# Sheet1.net
KiCad netlist of a schematic drawn in Altium Designer
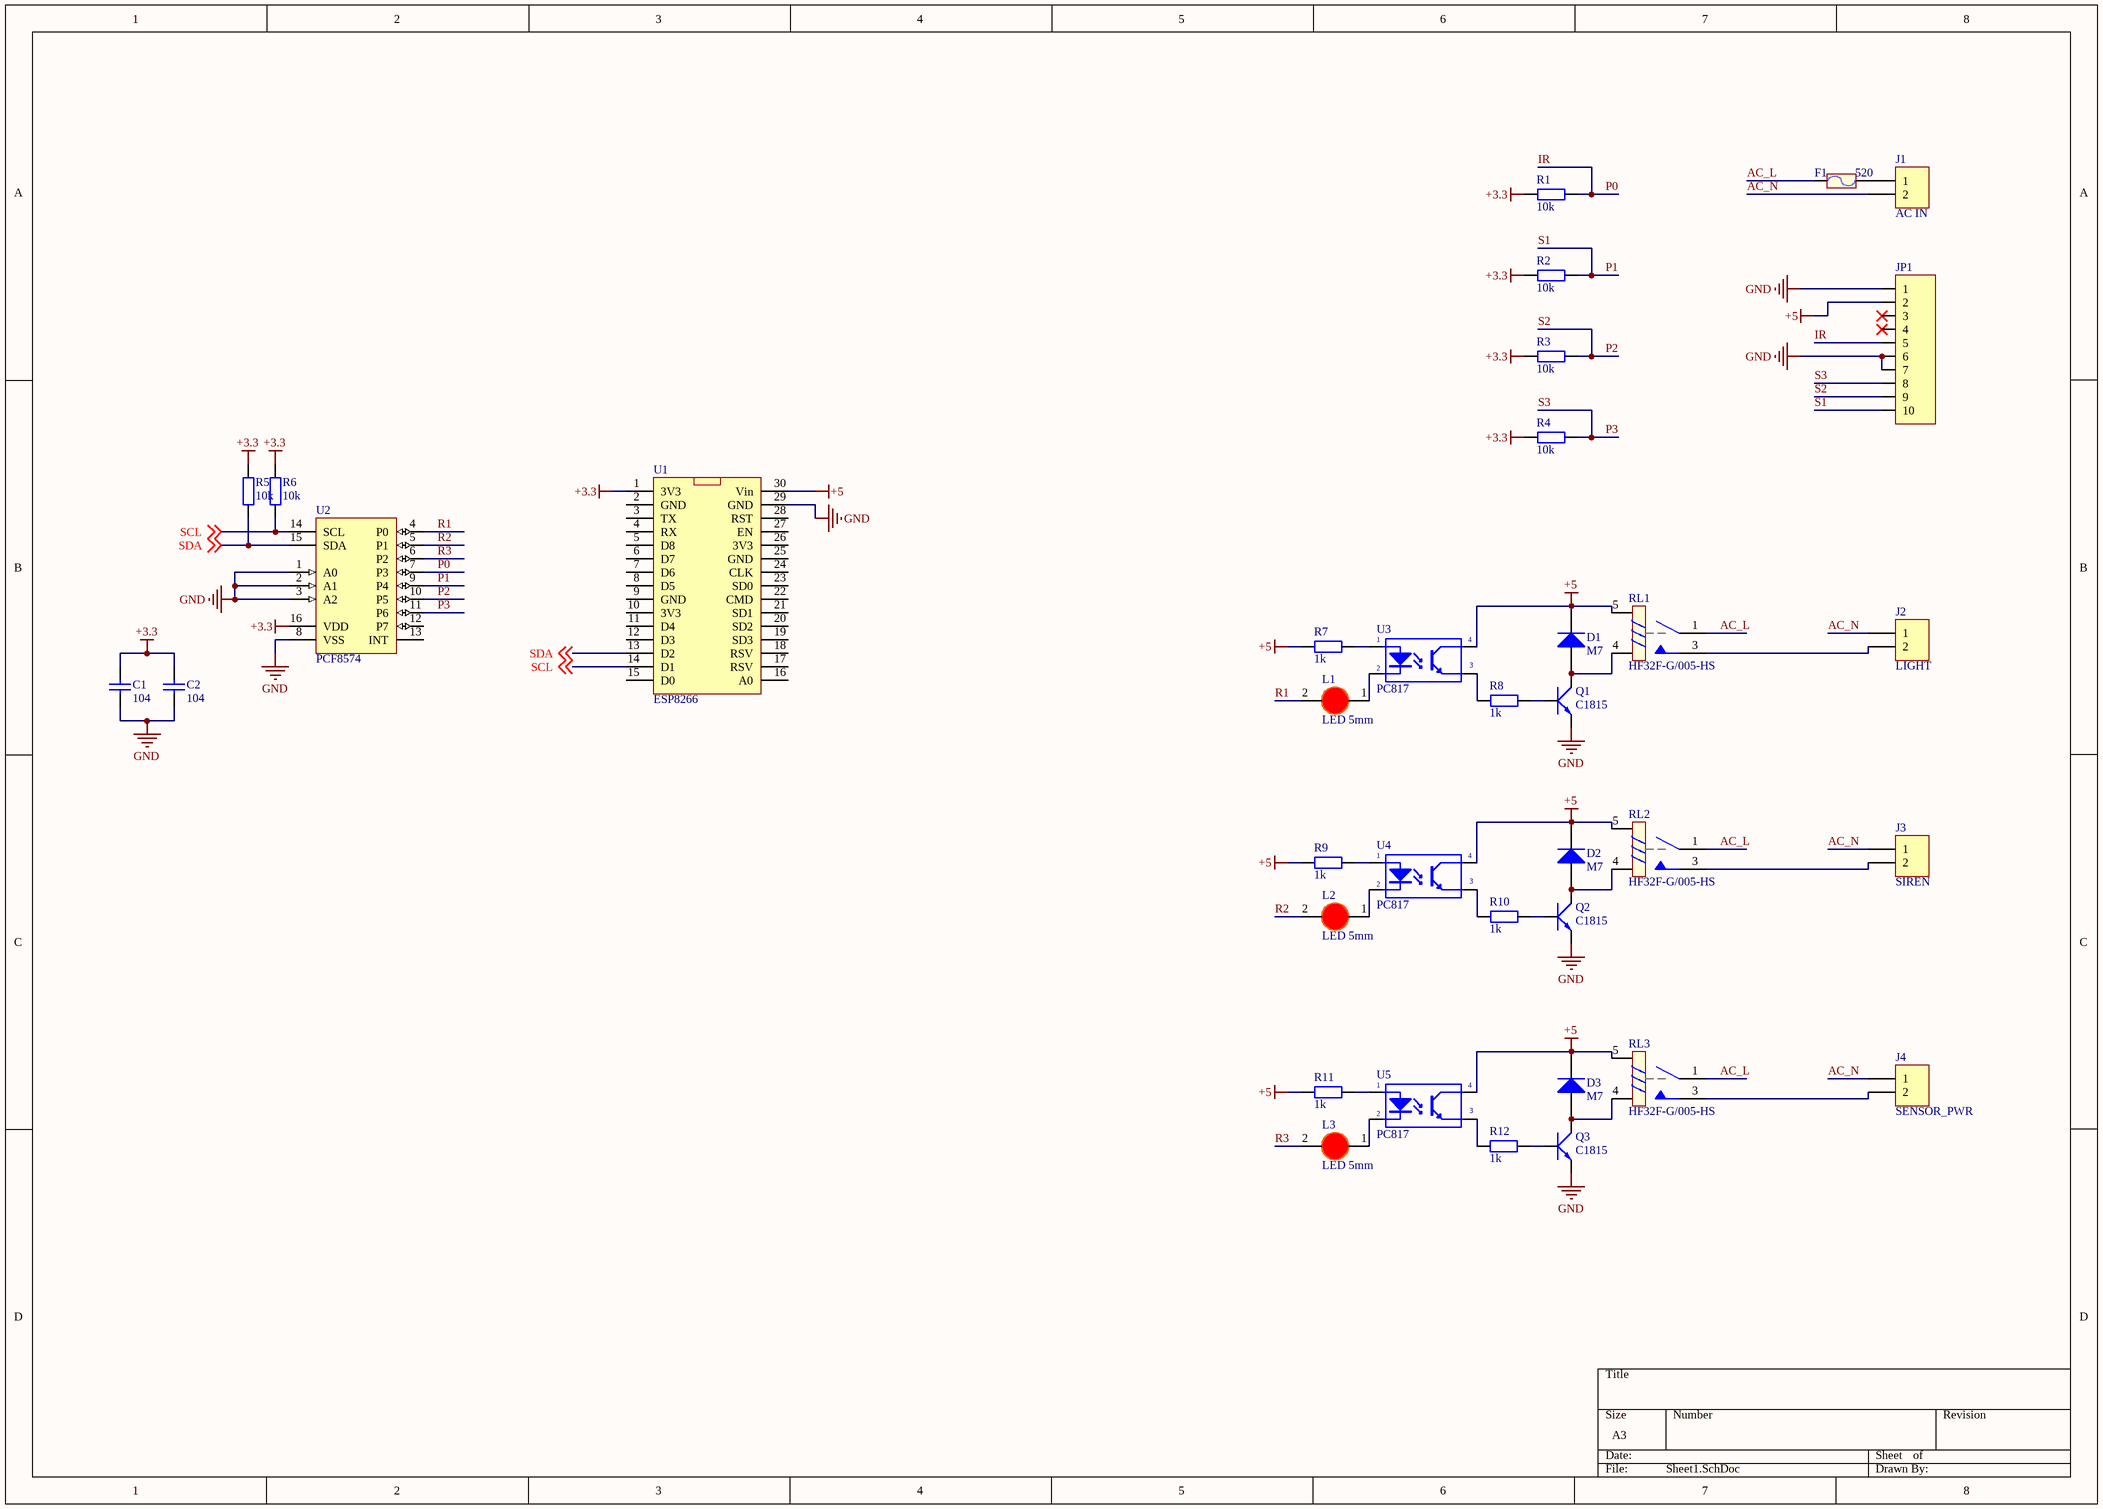
[diagram p0: Sheet1.SchDoc]

(export (version "E")
  (design (tool "Eeschema 10.0.6"))
  (components
    (comp (ref "C1")
      (value "104")
      (footprint "tu 0805")
      (description "Dán")
      (libsource (lib "Altium_Lib_by_KhueNguyenCreator") (part "Tu 0805 104 50V 10%"))
    )
    (comp (ref "C2")
      (value "104")
      (footprint "tu 0805")
      (description "Dán")
      (libsource (lib "Altium_Lib_by_KhueNguyenCreator") (part "Tu 0805 104 50V 10%"))
    )
    (comp (ref "D1")
      (value "M7")
      (footprint "DIODE SMA")
      (description "Dán")
      (libsource (lib "Altium_Lib_by_KhueNguyenCreator") (part "Diode M7 ( 4007 )"))
    )
    (comp (ref "D2")
      (value "M7")
      (footprint "DIODE SMA")
      (description "Dán")
      (libsource (lib "Altium_Lib_by_KhueNguyenCreator") (part "Diode M7 ( 4007 )"))
    )
    (comp (ref "D3")
      (value "M7")
      (footprint "DIODE SMA")
      (description "Dán")
      (libsource (lib "Altium_Lib_by_KhueNguyenCreator") (part "Diode M7 ( 4007 )"))
    )
    (comp (ref "F1")
      (value "520")
      (footprint "De Cau Chi 520 630")
      (description "5x20mm")
      (libsource (lib "Altium_Lib_by_KhueNguyenCreator") (part "De Cau Chi 520 630"))
    )
    (comp (ref "J1")
      (value "AC IN")
      (footprint "CON 2 2EDG5.08 B")
      (description "CON2 KF terminal")
      (libsource (lib "iuh-thuc-hanh") (part "CON 2 EDG5.08"))
    )
    (comp (ref "J2")
      (value "LIGHT")
      (footprint "CON 2 2EDG5.08 B")
      (description "CON2 KF terminal")
      (libsource (lib "iuh-thuc-hanh") (part "CON 2 EDG5.08"))
    )
    (comp (ref "J3")
      (value "SIREN")
      (footprint "CON 2 2EDG5.08 B")
      (description "CON2 KF terminal")
      (libsource (lib "iuh-thuc-hanh") (part "CON 2 EDG5.08"))
    )
    (comp (ref "J4")
      (value "SENSOR_PWR")
      (footprint "CON 2 2EDG5.08 B")
      (description "CON2 KF terminal")
      (libsource (lib "iuh-thuc-hanh") (part "CON 2 EDG5.08"))
    )
    (comp (ref "JP1")
      (value "JP 1x10 2.54")
      (footprint "JP 1x10 CC")
      (description "Cắm")
      (libsource (lib "Altium_Lib_by_KhueNguyenCreator") (part "JP 1x10 2.54 Cai Cong"))
    )
    (comp (ref "L1")
      (value "LED 5mm")
      (footprint "LED-5MM-RED")
      (description "Cắm")
      (libsource (lib "Altium_Lib_by_KhueNguyenCreator") (part "LED 5mm Do"))
    )
    (comp (ref "L2")
      (value "LED 5mm")
      (footprint "LED-5MM-RED")
      (description "Cắm")
      (libsource (lib "Altium_Lib_by_KhueNguyenCreator") (part "LED 5mm Do"))
    )
    (comp (ref "L3")
      (value "LED 5mm")
      (footprint "LED-5MM-RED")
      (description "Cắm")
      (libsource (lib "Altium_Lib_by_KhueNguyenCreator") (part "LED 5mm Do"))
    )
    (comp (ref "Q1")
      (value "C1815")
      (footprint "TO92")
      (description "NPN transistor")
      (libsource (lib "Altium_Lib_by_KhueNguyenCreator") (part "Trans C1815 DIP"))
    )
    (comp (ref "Q2")
      (value "C1815")
      (footprint "TO92")
      (description "NPN transistor")
      (libsource (lib "Altium_Lib_by_KhueNguyenCreator") (part "Trans C1815 DIP"))
    )
    (comp (ref "Q3")
      (value "C1815")
      (footprint "TO92")
      (description "NPN transistor")
      (libsource (lib "Altium_Lib_by_KhueNguyenCreator") (part "Trans C1815 DIP"))
    )
    (comp (ref "R1")
      (value "10k")
      (footprint "tro smd 0805")
      (description "Dán")
      (libsource (lib "Altium_Lib_by_KhueNguyenCreator") (part "Tro 0805 1% 10k"))
    )
    (comp (ref "R2")
      (value "10k")
      (footprint "tro smd 0805")
      (description "Dán")
      (libsource (lib "Altium_Lib_by_KhueNguyenCreator") (part "Tro 0805 1% 10k"))
    )
    (comp (ref "R3")
      (value "10k")
      (footprint "tro smd 0805")
      (description "Dán")
      (libsource (lib "Altium_Lib_by_KhueNguyenCreator") (part "Tro 0805 1% 10k"))
    )
    (comp (ref "R4")
      (value "10k")
      (footprint "tro smd 0805")
      (description "Dán")
      (libsource (lib "Altium_Lib_by_KhueNguyenCreator") (part "Tro 0805 1% 10k"))
    )
    (comp (ref "R5")
      (value "10k")
      (footprint "tro smd 0805")
      (description "Dán")
      (libsource (lib "Altium_Lib_by_KhueNguyenCreator") (part "Tro 0805 1% 10k"))
    )
    (comp (ref "R6")
      (value "10k")
      (footprint "tro smd 0805")
      (description "Dán")
      (libsource (lib "Altium_Lib_by_KhueNguyenCreator") (part "Tro 0805 1% 10k"))
    )
    (comp (ref "R7")
      (value "1k")
      (footprint "tro smd 0805")
      (description "Dán")
      (libsource (lib "Altium_Lib_by_KhueNguyenCreator") (part "Tro 0805 1% 1k"))
    )
    (comp (ref "R8")
      (value "1k")
      (footprint "tro smd 0805")
      (description "Dán")
      (libsource (lib "Altium_Lib_by_KhueNguyenCreator") (part "Tro 0805 1% 1k"))
    )
    (comp (ref "R9")
      (value "1k")
      (footprint "tro smd 0805")
      (description "Dán")
      (libsource (lib "Altium_Lib_by_KhueNguyenCreator") (part "Tro 0805 1% 1k"))
    )
    (comp (ref "R10")
      (value "1k")
      (footprint "tro smd 0805")
      (description "Dán")
      (libsource (lib "Altium_Lib_by_KhueNguyenCreator") (part "Tro 0805 1% 1k"))
    )
    (comp (ref "R11")
      (value "1k")
      (footprint "tro smd 0805")
      (description "Dán")
      (libsource (lib "Altium_Lib_by_KhueNguyenCreator") (part "Tro 0805 1% 1k"))
    )
    (comp (ref "R12")
      (value "1k")
      (footprint "tro smd 0805")
      (description "Dán")
      (libsource (lib "Altium_Lib_by_KhueNguyenCreator") (part "Tro 0805 1% 1k"))
    )
    (comp (ref "RL1")
      (value "HF32F-G/005-HS")
      (footprint "HF32F-G")
      (description "Relay hongfa 10A 4P HF32F-G/005-HS")
      (libsource (lib "iuh-thuc-hanh") (part "Relay HF 10A"))
    )
    (comp (ref "RL2")
      (value "HF32F-G/005-HS")
      (footprint "HF32F-G")
      (description "Relay hongfa 10A 4P HF32F-G/005-HS")
      (libsource (lib "iuh-thuc-hanh") (part "Relay HF 10A"))
    )
    (comp (ref "RL3")
      (value "HF32F-G/005-HS")
      (footprint "HF32F-G")
      (description "Relay hongfa 10A 4P HF32F-G/005-HS")
      (libsource (lib "iuh-thuc-hanh") (part "Relay HF 10A"))
    )
    (comp (ref "U1")
      (value "ESP8266")
      (footprint "NODE MCU CH340")
      (description "ESP8266 nodemcu 1.0")
      (libsource (lib "iuh-thuc-hanh") (part "NODEMCU 1.0"))
    )
    (comp (ref "U2") (value "PCF8574") (footprint "DIP16") (libsource (lib "iuh-thuc-hanh") (part "PCF8574")))
    (comp (ref "U3")
      (value "PC817")
      (footprint "DIP4")
      (description "Single Opto")
      (libsource (lib "LIBRARY1") (part "PC817"))
    )
    (comp (ref "U4")
      (value "PC817")
      (footprint "DIP4")
      (description "Single Opto")
      (libsource (lib "LIBRARY1") (part "PC817"))
    )
    (comp (ref "U5")
      (value "PC817")
      (footprint "DIP4")
      (description "Single Opto")
      (libsource (lib "LIBRARY1") (part "PC817"))
    )
  )
  (nets
    (net (code "1") (name "+3.3") (class "Default")
      (node (ref "C1") (pin "1") (pinfunction "1_1") (pintype "passive"))
      (node (ref "C2") (pin "1") (pinfunction "1_1") (pintype "passive"))
      (node (ref "R1") (pin "1") (pinfunction "1_1") (pintype "passive"))
      (node (ref "R2") (pin "1") (pinfunction "1_1") (pintype "passive"))
      (node (ref "R3") (pin "1") (pinfunction "1_1") (pintype "passive"))
      (node (ref "R4") (pin "1") (pinfunction "1_1") (pintype "passive"))
      (node (ref "R5") (pin "2") (pinfunction "2_2") (pintype "passive"))
      (node (ref "R6") (pin "2") (pinfunction "2_2") (pintype "passive"))
      (node (ref "U1") (pin "1") (pinfunction "3V3_1") (pintype "passive"))
      (node (ref "U2") (pin "16") (pinfunction "VDD_16") (pintype "passive"))
    )
    (net (code "2") (name "+5") (class "Default")
      (node (ref "D1") (pin "2") (pinfunction "K_2") (pintype "passive"))
      (node (ref "D2") (pin "2") (pinfunction "K_2") (pintype "passive"))
      (node (ref "D3") (pin "2") (pinfunction "K_2") (pintype "passive"))
      (node (ref "JP1") (pin "2") (pinfunction "2_2") (pintype "passive"))
      (node (ref "R11") (pin "1") (pinfunction "1_1") (pintype "passive"))
      (node (ref "R7") (pin "1") (pinfunction "1_1") (pintype "passive"))
      (node (ref "R9") (pin "1") (pinfunction "1_1") (pintype "passive"))
      (node (ref "RL1") (pin "5") (pinfunction "5_5") (pintype "passive"))
      (node (ref "RL2") (pin "5") (pinfunction "5_5") (pintype "passive"))
      (node (ref "RL3") (pin "5") (pinfunction "5_5") (pintype "passive"))
      (node (ref "U1") (pin "30") (pinfunction "Vin_30") (pintype "passive"))
      (node (ref "U3") (pin "4") (pinfunction "C_4") (pintype "passive"))
      (node (ref "U4") (pin "4") (pinfunction "C_4") (pintype "passive"))
      (node (ref "U5") (pin "4") (pinfunction "C_4") (pintype "passive"))
    )
    (net (code "3") (name "/AC_L") (class "Default")
      (node (ref "F1") (pin "1") (pinfunction "1_1") (pintype "passive"))
      (node (ref "RL1") (pin "1") (pinfunction "1_1") (pintype "passive"))
      (node (ref "RL2") (pin "1") (pinfunction "1_1") (pintype "passive"))
      (node (ref "RL3") (pin "1") (pinfunction "1_1") (pintype "passive"))
    )
    (net (code "4") (name "/AC_N") (class "Default")
      (node (ref "J1") (pin "2") (pinfunction "2_2") (pintype "passive"))
      (node (ref "J2") (pin "1") (pinfunction "1_1") (pintype "passive"))
      (node (ref "J3") (pin "1") (pinfunction "1_1") (pintype "passive"))
      (node (ref "J4") (pin "1") (pinfunction "1_1") (pintype "passive"))
    )
    (net (code "5") (name "/IR") (class "Default")
      (node (ref "JP1") (pin "5") (pinfunction "5_5") (pintype "passive"))
      (node (ref "R1") (pin "2") (pinfunction "2_2") (pintype "passive"))
      (node (ref "U2") (pin "7") (pinfunction "P3_7") (pintype "bidirectional"))
    )
    (net (code "6") (name "/P1") (class "Default")
      (node (ref "JP1") (pin "10") (pinfunction "10_10") (pintype "passive"))
      (node (ref "R2") (pin "2") (pinfunction "2_2") (pintype "passive"))
      (node (ref "U2") (pin "9") (pinfunction "P4_9") (pintype "bidirectional"))
    )
    (net (code "7") (name "/P2") (class "Default")
      (node (ref "JP1") (pin "9") (pinfunction "9_9") (pintype "passive"))
      (node (ref "R3") (pin "2") (pinfunction "2_2") (pintype "passive"))
      (node (ref "U2") (pin "10") (pinfunction "P5_10") (pintype "bidirectional"))
    )
    (net (code "8") (name "/P3") (class "Default")
      (node (ref "JP1") (pin "8") (pinfunction "8_8") (pintype "passive"))
      (node (ref "R4") (pin "2") (pinfunction "2_2") (pintype "passive"))
      (node (ref "U2") (pin "11") (pinfunction "P6_11") (pintype "bidirectional"))
    )
    (net (code "9") (name "/R1") (class "Default")
      (node (ref "L1") (pin "2") (pinfunction "K_2") (pintype "passive"))
      (node (ref "U2") (pin "4") (pinfunction "P0_4") (pintype "bidirectional"))
    )
    (net (code "10") (name "/R2") (class "Default")
      (node (ref "L2") (pin "2") (pinfunction "K_2") (pintype "passive"))
      (node (ref "U2") (pin "5") (pinfunction "P1_5") (pintype "bidirectional"))
    )
    (net (code "11") (name "/R3") (class "Default")
      (node (ref "L3") (pin "2") (pinfunction "K_2") (pintype "passive"))
      (node (ref "U2") (pin "6") (pinfunction "P2_6") (pintype "bidirectional"))
    )
    (net (code "12") (name "GND") (class "Default")
      (node (ref "C1") (pin "2") (pinfunction "2_2") (pintype "passive"))
      (node (ref "C2") (pin "2") (pinfunction "2_2") (pintype "passive"))
      (node (ref "JP1") (pin "1") (pinfunction "1_1") (pintype "passive"))
      (node (ref "JP1") (pin "6") (pinfunction "6_6") (pintype "passive"))
      (node (ref "JP1") (pin "7") (pinfunction "7_7") (pintype "passive"))
      (node (ref "Q1") (pin "1") (pinfunction "E_1") (pintype "passive"))
      (node (ref "Q2") (pin "1") (pinfunction "E_1") (pintype "passive"))
      (node (ref "Q3") (pin "1") (pinfunction "E_1") (pintype "passive"))
      (node (ref "U1") (pin "29") (pinfunction "GND_29") (pintype "passive"))
      (node (ref "U2") (pin "1") (pinfunction "A0_1") (pintype "input"))
      (node (ref "U2") (pin "2") (pinfunction "A1_2") (pintype "input"))
      (node (ref "U2") (pin "3") (pinfunction "A2_3") (pintype "input"))
      (node (ref "U2") (pin "8") (pinfunction "VSS_8") (pintype "passive"))
    )
    (net (code "13") (name "Net-(D1-A)") (class "Default")
      (node (ref "D1") (pin "1") (pinfunction "A_1") (pintype "passive"))
      (node (ref "Q1") (pin "2") (pinfunction "C_2") (pintype "passive"))
      (node (ref "RL1") (pin "4") (pinfunction "4_4") (pintype "passive"))
    )
    (net (code "14") (name "Net-(D2-A)") (class "Default")
      (node (ref "D2") (pin "1") (pinfunction "A_1") (pintype "passive"))
      (node (ref "Q2") (pin "2") (pinfunction "C_2") (pintype "passive"))
      (node (ref "RL2") (pin "4") (pinfunction "4_4") (pintype "passive"))
    )
    (net (code "15") (name "Net-(D3-A)") (class "Default")
      (node (ref "D3") (pin "1") (pinfunction "A_1") (pintype "passive"))
      (node (ref "Q3") (pin "2") (pinfunction "C_2") (pintype "passive"))
      (node (ref "RL3") (pin "4") (pinfunction "4_4") (pintype "passive"))
    )
    (net (code "16") (name "Net-(F1-Pad2)") (class "Default")
      (node (ref "F1") (pin "2") (pinfunction "2_2") (pintype "passive"))
      (node (ref "J1") (pin "1") (pinfunction "1_1") (pintype "passive"))
    )
    (net (code "17") (name "Net-(J2-Pad2)") (class "Default")
      (node (ref "J2") (pin "2") (pinfunction "2_2") (pintype "passive"))
      (node (ref "RL1") (pin "3") (pinfunction "3_3") (pintype "passive"))
    )
    (net (code "18") (name "Net-(J3-Pad2)") (class "Default")
      (node (ref "J3") (pin "2") (pinfunction "2_2") (pintype "passive"))
      (node (ref "RL2") (pin "3") (pinfunction "3_3") (pintype "passive"))
    )
    (net (code "19") (name "Net-(J4-Pad2)") (class "Default")
      (node (ref "J4") (pin "2") (pinfunction "2_2") (pintype "passive"))
      (node (ref "RL3") (pin "3") (pinfunction "3_3") (pintype "passive"))
    )
    (net (code "20") (name "Net-(L1-A)") (class "Default")
      (node (ref "L1") (pin "1") (pinfunction "A_1") (pintype "passive"))
      (node (ref "U3") (pin "2") (pinfunction "K_2") (pintype "passive"))
    )
    (net (code "21") (name "Net-(L2-A)") (class "Default")
      (node (ref "L2") (pin "1") (pinfunction "A_1") (pintype "passive"))
      (node (ref "U4") (pin "2") (pinfunction "K_2") (pintype "passive"))
    )
    (net (code "22") (name "Net-(L3-A)") (class "Default")
      (node (ref "L3") (pin "1") (pinfunction "A_1") (pintype "passive"))
      (node (ref "U5") (pin "2") (pinfunction "K_2") (pintype "passive"))
    )
    (net (code "23") (name "Net-(Q1-B)") (class "Default")
      (node (ref "Q1") (pin "3") (pinfunction "B_3") (pintype "passive"))
      (node (ref "R8") (pin "2") (pinfunction "2_2") (pintype "passive"))
    )
    (net (code "24") (name "Net-(Q2-B)") (class "Default")
      (node (ref "Q2") (pin "3") (pinfunction "B_3") (pintype "passive"))
      (node (ref "R10") (pin "2") (pinfunction "2_2") (pintype "passive"))
    )
    (net (code "25") (name "Net-(Q3-B)") (class "Default")
      (node (ref "Q3") (pin "3") (pinfunction "B_3") (pintype "passive"))
      (node (ref "R12") (pin "2") (pinfunction "2_2") (pintype "passive"))
    )
    (net (code "26") (name "Net-(U3-A)") (class "Default")
      (node (ref "R7") (pin "2") (pinfunction "2_2") (pintype "passive"))
      (node (ref "U3") (pin "1") (pinfunction "A_1") (pintype "passive"))
    )
    (net (code "27") (name "Net-(U3-E)") (class "Default")
      (node (ref "R8") (pin "1") (pinfunction "1_1") (pintype "passive"))
      (node (ref "U3") (pin "3") (pinfunction "E_3") (pintype "passive"))
    )
    (net (code "28") (name "Net-(U4-A)") (class "Default")
      (node (ref "R9") (pin "2") (pinfunction "2_2") (pintype "passive"))
      (node (ref "U4") (pin "1") (pinfunction "A_1") (pintype "passive"))
    )
    (net (code "29") (name "Net-(U4-E)") (class "Default")
      (node (ref "R10") (pin "1") (pinfunction "1_1") (pintype "passive"))
      (node (ref "U4") (pin "3") (pinfunction "E_3") (pintype "passive"))
    )
    (net (code "30") (name "Net-(U5-A)") (class "Default")
      (node (ref "R11") (pin "2") (pinfunction "2_2") (pintype "passive"))
      (node (ref "U5") (pin "1") (pinfunction "A_1") (pintype "passive"))
    )
    (net (code "31") (name "Net-(U5-E)") (class "Default")
      (node (ref "R12") (pin "1") (pinfunction "1_1") (pintype "passive"))
      (node (ref "U5") (pin "3") (pinfunction "E_3") (pintype "passive"))
    )
    (net (code "32") (name "SCL") (class "Default")
      (node (ref "R6") (pin "1") (pinfunction "1_1") (pintype "passive"))
      (node (ref "U1") (pin "14") (pinfunction "D1_14") (pintype "passive"))
      (node (ref "U2") (pin "14") (pinfunction "SCL_14") (pintype "passive"))
    )
    (net (code "33") (name "SDA") (class "Default")
      (node (ref "R5") (pin "1") (pinfunction "1_1") (pintype "passive"))
      (node (ref "U1") (pin "13") (pinfunction "D2_13") (pintype "passive"))
      (node (ref "U2") (pin "15") (pinfunction "SDA_15") (pintype "passive"))
    )
    (net (code "34") (name "unconnected-(JP1-Pad3)") (class "Default")
      (node (ref "JP1") (pin "3") (pinfunction "3_3") (pintype "passive+no_connect"))
    )
    (net (code "35") (name "unconnected-(JP1-Pad4)") (class "Default")
      (node (ref "JP1") (pin "4") (pinfunction "4_4") (pintype "passive+no_connect"))
    )
    (net (code "36") (name "unconnected-(U1-3V3-Pad10)") (class "Default")
      (node (ref "U1") (pin "10") (pinfunction "3V3_10") (pintype "passive"))
    )
    (net (code "37") (name "unconnected-(U1-3V3-Pad26)") (class "Default")
      (node (ref "U1") (pin "26") (pinfunction "3V3_26") (pintype "passive"))
    )
    (net (code "38") (name "unconnected-(U1-A0-Pad16)") (class "Default")
      (node (ref "U1") (pin "16") (pinfunction "A0_16") (pintype "passive"))
    )
    (net (code "39") (name "unconnected-(U1-CLK-Pad24)") (class "Default")
      (node (ref "U1") (pin "24") (pinfunction "CLK_24") (pintype "passive"))
    )
    (net (code "40") (name "unconnected-(U1-CMD-Pad22)") (class "Default")
      (node (ref "U1") (pin "22") (pinfunction "CMD_22") (pintype "passive"))
    )
    (net (code "41") (name "unconnected-(U1-D0-Pad15)") (class "Default")
      (node (ref "U1") (pin "15") (pinfunction "D0_15") (pintype "passive"))
    )
    (net (code "42") (name "unconnected-(U1-D3-Pad12)") (class "Default")
      (node (ref "U1") (pin "12") (pinfunction "D3_12") (pintype "passive"))
    )
    (net (code "43") (name "unconnected-(U1-D4-Pad11)") (class "Default")
      (node (ref "U1") (pin "11") (pinfunction "D4_11") (pintype "passive"))
    )
    (net (code "44") (name "unconnected-(U1-D5-Pad8)") (class "Default")
      (node (ref "U1") (pin "8") (pinfunction "D5_8") (pintype "passive"))
    )
    (net (code "45") (name "unconnected-(U1-D6-Pad7)") (class "Default")
      (node (ref "U1") (pin "7") (pinfunction "D6_7") (pintype "passive"))
    )
    (net (code "46") (name "unconnected-(U1-D7-Pad6)") (class "Default")
      (node (ref "U1") (pin "6") (pinfunction "D7_6") (pintype "passive"))
    )
    (net (code "47") (name "unconnected-(U1-D8-Pad5)") (class "Default")
      (node (ref "U1") (pin "5") (pinfunction "D8_5") (pintype "passive"))
    )
    (net (code "48") (name "unconnected-(U1-EN-Pad27)") (class "Default")
      (node (ref "U1") (pin "27") (pinfunction "EN_27") (pintype "passive"))
    )
    (net (code "49") (name "unconnected-(U1-GND-Pad2)") (class "Default")
      (node (ref "U1") (pin "2") (pinfunction "GND_2") (pintype "passive"))
    )
    (net (code "50") (name "unconnected-(U1-GND-Pad9)") (class "Default")
      (node (ref "U1") (pin "9") (pinfunction "GND_9") (pintype "passive"))
    )
    (net (code "51") (name "unconnected-(U1-GND-Pad25)") (class "Default")
      (node (ref "U1") (pin "25") (pinfunction "GND_25") (pintype "passive"))
    )
    (net (code "52") (name "unconnected-(U1-RST-Pad28)") (class "Default")
      (node (ref "U1") (pin "28") (pinfunction "RST_28") (pintype "passive"))
    )
    (net (code "53") (name "unconnected-(U1-RSV-Pad17)") (class "Default")
      (node (ref "U1") (pin "17") (pinfunction "RSV_17") (pintype "passive"))
    )
    (net (code "54") (name "unconnected-(U1-RSV-Pad18)") (class "Default")
      (node (ref "U1") (pin "18") (pinfunction "RSV_18") (pintype "passive"))
    )
    (net (code "55") (name "unconnected-(U1-RX-Pad4)") (class "Default")
      (node (ref "U1") (pin "4") (pinfunction "RX_4") (pintype "passive"))
    )
    (net (code "56") (name "unconnected-(U1-SD0-Pad23)") (class "Default")
      (node (ref "U1") (pin "23") (pinfunction "SD0_23") (pintype "passive"))
    )
    (net (code "57") (name "unconnected-(U1-SD1-Pad21)") (class "Default")
      (node (ref "U1") (pin "21") (pinfunction "SD1_21") (pintype "passive"))
    )
    (net (code "58") (name "unconnected-(U1-SD2-Pad20)") (class "Default")
      (node (ref "U1") (pin "20") (pinfunction "SD2_20") (pintype "passive"))
    )
    (net (code "59") (name "unconnected-(U1-SD3-Pad19)") (class "Default")
      (node (ref "U1") (pin "19") (pinfunction "SD3_19") (pintype "passive"))
    )
    (net (code "60") (name "unconnected-(U1-TX-Pad3)") (class "Default")
      (node (ref "U1") (pin "3") (pinfunction "TX_3") (pintype "passive"))
    )
    (net (code "61") (name "unconnected-(U2-INT-Pad13)") (class "Default")
      (node (ref "U2") (pin "13") (pinfunction "INT_13") (pintype "passive"))
    )
    (net (code "62") (name "unconnected-(U2-P7-Pad12)") (class "Default")
      (node (ref "U2") (pin "12") (pinfunction "P7_12") (pintype "bidirectional"))
    )
  )
)
